# Light_source_driver_board_circuit_diagra.net
KiCad netlist of a schematic drawn in Altium Designer
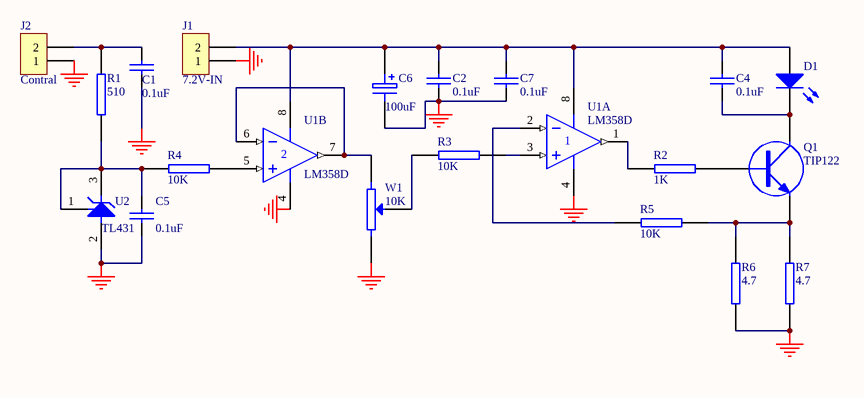
[diagram p0: Light source driver board circuit diagram.SchDoc]

(export (version "E")
  (design (tool "Eeschema 10.0.6"))
  (components
    (comp (ref "C1")
      (value "0.1uF")
      (footprint "0805")
      (description "Capacitor")
      (libsource (lib "*") (part "CAP"))
    )
    (comp (ref "C2")
      (value "0.1uF")
      (footprint "0805")
      (description "Capacitor")
      (libsource (lib "*") (part "CAP"))
    )
    (comp (ref "C4")
      (value "0.1uF")
      (footprint "0805")
      (description "Capacitor")
      (libsource (lib "*") (part "CAP"))
    )
    (comp (ref "C5")
      (value "0.1uF")
      (footprint "0805")
      (description "Capacitor")
      (libsource (lib "*") (part "CAP"))
    )
    (comp (ref "C6")
      (value "100uF")
      (footprint "7243")
      (description "Electrolytic Capacitor")
      (libsource (lib "*") (part "ELECTRO1"))
    )
    (comp (ref "C7")
      (value "0.1uF")
      (footprint "0805")
      (description "Capacitor")
      (libsource (lib "*") (part "CAP"))
    )
    (comp (ref "D1")
      (value "~")
      (footprint "LED-1")
      (description "Typical RED GaAs LED")
      (fields (field (name "PUBLISHER") "Altium Limited"))
      (libsource (lib "Miscellaneous Devices") (part "LED1"))
    )
    (comp (ref "J1")
      (value "7.2V-IN")
      (footprint "XH2.54-2P_直")
      (description "Connector")
      (libsource (lib "*") (part "CON2"))
    )
    (comp (ref "J2")
      (value "Contral")
      (footprint "XH2.54-2P_直")
      (description "Connector")
      (libsource (lib "*") (part "CON2"))
    )
    (comp (ref "Q1")
      (value "TIP122")
      (footprint "TO220H")
      (description "NPN Transistor")
      (libsource (lib "*") (part "NPN"))
    )
    (comp (ref "R1") (value "510") (footprint "0805") (libsource (lib "*") (part "RES2")))
    (comp (ref "R2") (value "1K") (footprint "0805") (libsource (lib "*") (part "RES2")))
    (comp (ref "R3") (value "10K") (footprint "0805") (libsource (lib "*") (part "RES2")))
    (comp (ref "R4") (value "10K") (footprint "0805") (libsource (lib "*") (part "RES2")))
    (comp (ref "R5") (value "10K") (footprint "0805") (libsource (lib "*") (part "RES2")))
    (comp (ref "R6") (value "4.7") (footprint "1210") (libsource (lib "*") (part "RES2")))
    (comp (ref "R7") (value "4.7") (footprint "1210") (libsource (lib "*") (part "RES2")))
    (comp (ref "U1")
      (value "LM358D")
      (footprint "SO-8")
      (description "Dual Low-Power Operational Amplifier")
      (fields (field (name "PUBLISHER") "Altium Limited"))
      (libsource (lib "Motorola Amplifier Operational Amplifier") (part "LM358D"))
    )
    (comp (ref "U2")
      (value "TL431")
      (footprint "SOT-89_M")
      (description "Adjustable Precision Shunt Regulator")
      (libsource (lib "*") (part "TL431"))
    )
    (comp (ref "W1")
      (value "10K")
      (footprint "VR")
      (description "Potentiometer")
      (libsource (lib "*") (part "POT2"))
    )
  )
  (nets
    (net (code "1") (name "GND") (class "Default")
      (node (ref "C1") (pin "1") (pinfunction "1_1") (pintype "passive"))
      (node (ref "C2") (pin "2") (pinfunction "2_2") (pintype "passive"))
      (node (ref "C5") (pin "1") (pinfunction "1_1") (pintype "passive"))
      (node (ref "C6") (pin "2") (pinfunction "2_2") (pintype "passive"))
      (node (ref "C7") (pin "2") (pinfunction "2_2") (pintype "passive"))
      (node (ref "J1") (pin "1") (pinfunction "1_1") (pintype "passive"))
      (node (ref "J2") (pin "1") (pinfunction "1_1") (pintype "passive"))
      (node (ref "R6") (pin "2") (pinfunction "2_2") (pintype "passive"))
      (node (ref "R7") (pin "2") (pinfunction "2_2") (pintype "passive"))
      (node (ref "U1") (pin "4") (pinfunction "V-_4") (pintype "power_in"))
      (node (ref "U2") (pin "2") (pinfunction "A_2") (pintype "passive"))
      (node (ref "W1") (pin "2") (pinfunction "2_2") (pintype "passive"))
    )
    (net (code "2") (name "Net-(C1-Pad2)") (class "Default")
      (node (ref "C1") (pin "2") (pinfunction "2_2") (pintype "passive"))
      (node (ref "J2") (pin "2") (pinfunction "2_2") (pintype "passive"))
      (node (ref "R1") (pin "1") (pinfunction "1_1") (pintype "passive"))
    )
    (net (code "3") (name "Net-(D1-A)") (class "Default")
      (node (ref "C2") (pin "1") (pinfunction "1_1") (pintype "passive"))
      (node (ref "C4") (pin "1") (pinfunction "1_1") (pintype "passive"))
      (node (ref "C6") (pin "1") (pinfunction "1_1") (pintype "passive"))
      (node (ref "C7") (pin "1") (pinfunction "1_1") (pintype "passive"))
      (node (ref "D1") (pin "1") (pinfunction "A_1") (pintype "passive"))
      (node (ref "J1") (pin "2") (pinfunction "2_2") (pintype "passive"))
      (node (ref "U1") (pin "8") (pinfunction "V+_8") (pintype "power_in"))
    )
    (net (code "4") (name "Net-(D1-K)") (class "Default")
      (node (ref "C4") (pin "2") (pinfunction "2_2") (pintype "passive"))
      (node (ref "D1") (pin "2") (pinfunction "K_2") (pintype "passive"))
      (node (ref "Q1") (pin "2") (pinfunction "C_2") (pintype "passive"))
    )
    (net (code "5") (name "Net-(Q1-B)") (class "Default")
      (node (ref "Q1") (pin "1") (pinfunction "B_1") (pintype "passive"))
      (node (ref "R2") (pin "2") (pinfunction "2_2") (pintype "passive"))
    )
    (net (code "6") (name "Net-(Q1-E)") (class "Default")
      (node (ref "Q1") (pin "3") (pinfunction "E_3") (pintype "passive"))
      (node (ref "R5") (pin "1") (pinfunction "1_1") (pintype "passive"))
      (node (ref "R6") (pin "1") (pinfunction "1_1") (pintype "passive"))
      (node (ref "R7") (pin "1") (pinfunction "1_1") (pintype "passive"))
    )
    (net (code "7") (name "Net-(U1A-IN+)") (class "Default")
      (node (ref "R3") (pin "2") (pinfunction "2_2") (pintype "passive"))
      (node (ref "U1") (pin "3") (pinfunction "IN+_3") (pintype "input"))
    )
    (net (code "8") (name "Net-(U1A-IN-)") (class "Default")
      (node (ref "R5") (pin "2") (pinfunction "2_2") (pintype "passive"))
      (node (ref "U1") (pin "2") (pinfunction "IN-_2") (pintype "input"))
    )
    (net (code "9") (name "Net-(U1A-OUT)") (class "Default")
      (node (ref "R2") (pin "1") (pinfunction "1_1") (pintype "passive"))
      (node (ref "U1") (pin "1") (pinfunction "OUT_1") (pintype "output"))
    )
    (net (code "10") (name "Net-(U1B-IN+)") (class "Default")
      (node (ref "R4") (pin "2") (pinfunction "2_2") (pintype "passive"))
      (node (ref "U1") (pin "5") (pinfunction "IN+_5") (pintype "input"))
    )
    (net (code "11") (name "Net-(U1B-IN-)") (class "Default")
      (node (ref "U1") (pin "6") (pinfunction "IN-_6") (pintype "input"))
      (node (ref "U1") (pin "7") (pinfunction "OUT_7") (pintype "output"))
      (node (ref "W1") (pin "1") (pinfunction "1_1") (pintype "passive"))
    )
    (net (code "12") (name "Net-(U2-K)") (class "Default")
      (node (ref "C5") (pin "2") (pinfunction "2_2") (pintype "passive"))
      (node (ref "R1") (pin "2") (pinfunction "2_2") (pintype "passive"))
      (node (ref "R4") (pin "1") (pinfunction "1_1") (pintype "passive"))
      (node (ref "U2") (pin "1") (pinfunction "R_1") (pintype "passive"))
      (node (ref "U2") (pin "3") (pinfunction "K_3") (pintype "passive"))
    )
    (net (code "13") (name "Net-(W1-W)") (class "Default")
      (node (ref "R3") (pin "1") (pinfunction "1_1") (pintype "passive"))
      (node (ref "W1") (pin "3") (pinfunction "W_3") (pintype "passive"))
    )
  )
)
